# Peripherals.net
KiCad netlist of a schematic drawn in Altium Designer
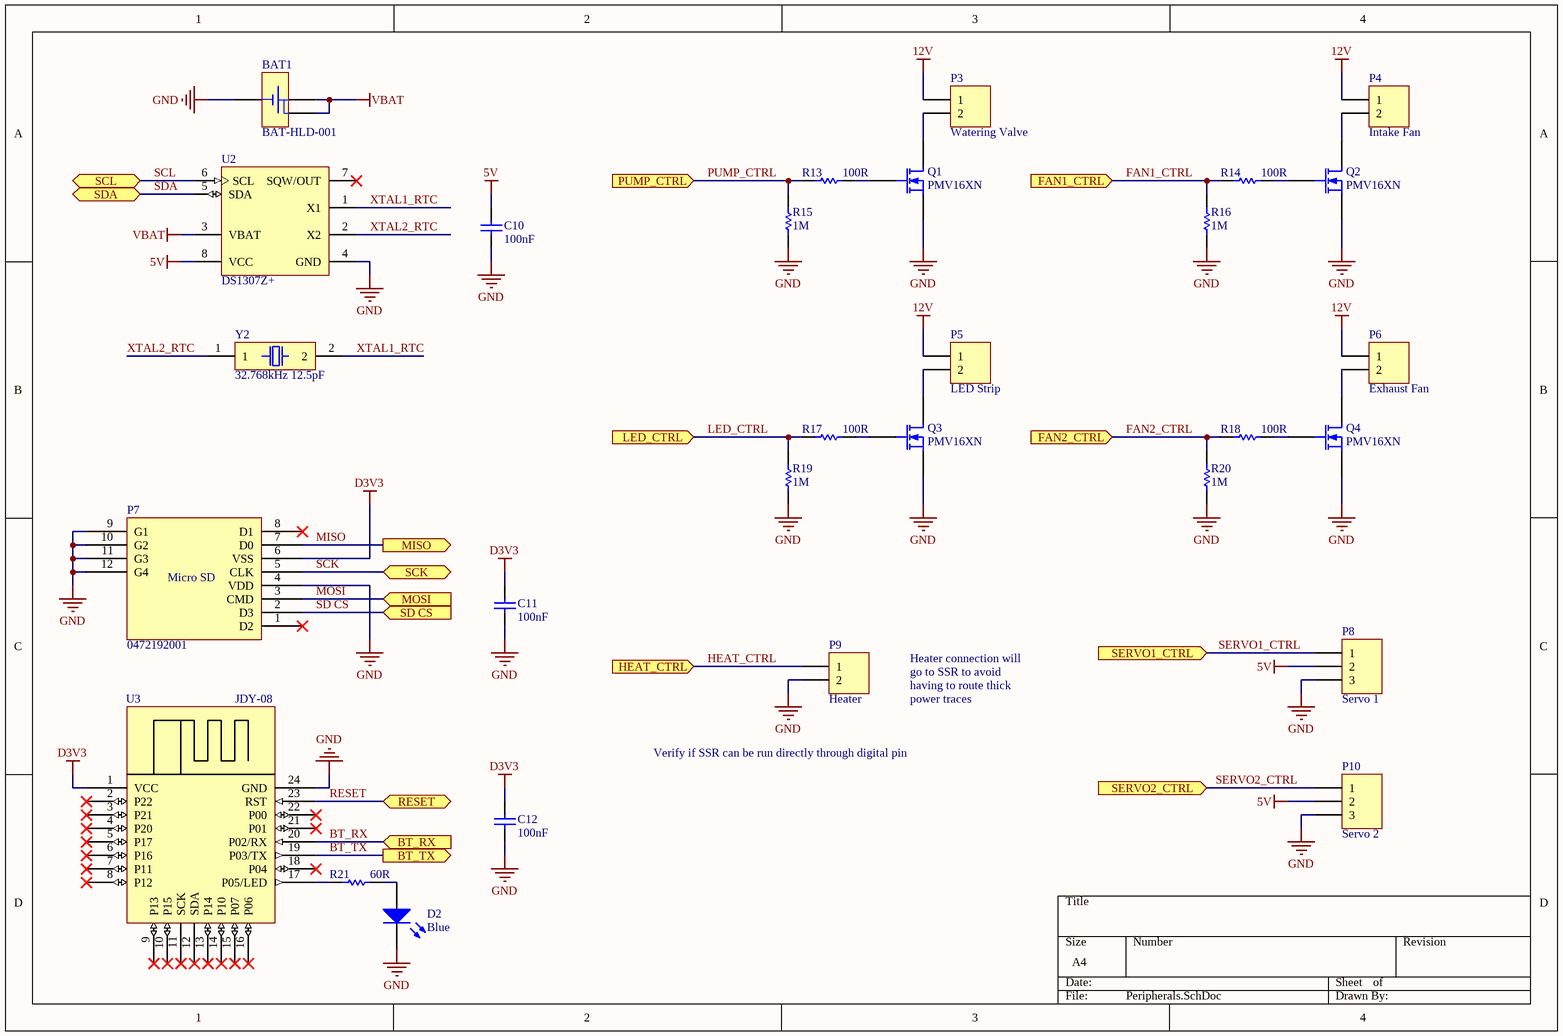
[diagram p0: Peripherals.SchDoc]

(export (version "E")
  (design (tool "Eeschema 10.0.6"))
  (components
    (comp (ref "BAT1")
      (value "BAT-HLD-001")
      (footprint "BATHLD-001")
      (description "20mm Coin Cell Battery Holder")
      (libsource (lib "Altium Content Vault") (part "BATHLD-001"))
    )
    (comp (ref "C10")
      (value "100nF")
      (footprint "CAP0603")
      (description "Capacitor")
      (fields (field (name "PUBLISHER") "Altium Limited"))
      (libsource (lib "Taiv") (part "Capacitor"))
    )
    (comp (ref "C11")
      (value "100nF")
      (footprint "CAP0603")
      (description "Capacitor")
      (fields (field (name "PUBLISHER") "Altium Limited"))
      (libsource (lib "Taiv") (part "Capacitor"))
    )
    (comp (ref "C12")
      (value "100nF")
      (footprint "CAP0603")
      (description "Capacitor")
      (fields (field (name "PUBLISHER") "Altium Limited"))
      (libsource (lib "Taiv") (part "Capacitor"))
    )
    (comp (ref "D2")
      (value "Blue")
      (footprint "DIODE0603")
      (description "Light Emitting Diode")
      (fields (field (name "PUBLISHER") "Altium Limited"))
      (libsource (lib "Taiv") (part "LED"))
    )
    (comp (ref "P3")
      (value "Watering Valve")
      (footprint "MOLEX MICROLATCH 2CT")
      (description "Header, 2-Pin")
      (fields (field (name "PUBLISHER") "Altium Limited"))
      (libsource (lib "Taiv") (part "2X1 2.54MM"))
    )
    (comp (ref "P4")
      (value "Intake Fan")
      (footprint "MOLEX MICROLATCH 2CT")
      (description "Header, 2-Pin")
      (fields (field (name "PUBLISHER") "Altium Limited"))
      (libsource (lib "Taiv") (part "2X1 2.54MM"))
    )
    (comp (ref "P5")
      (value "LED Strip")
      (footprint "MOLEX MICROLATCH 2CT")
      (description "Header, 2-Pin")
      (fields (field (name "PUBLISHER") "Altium Limited"))
      (libsource (lib "Taiv") (part "2X1 2.54MM"))
    )
    (comp (ref "P6")
      (value "Exhaust Fan")
      (footprint "MOLEX MICROLATCH 2CT")
      (description "Header, 2-Pin")
      (fields (field (name "PUBLISHER") "Altium Limited"))
      (libsource (lib "Taiv") (part "2X1 2.54MM"))
    )
    (comp (ref "P7")
      (value "0472192001")
      (footprint "MOLEX MICRO SD")
      (description "Micro SD Card")
      (libsource (lib "Taiv") (part "Micro SD Card"))
    )
    (comp (ref "P8")
      (value "Servo 1")
      (footprint "MOLEX MICROLATCH 3CT")
      (description "Header, 3-Pin")
      (fields (field (name "PUBLISHER") "Altium Limited"))
      (libsource (lib "Taiv") (part "3X1 2.54MM"))
    )
    (comp (ref "P9")
      (value "Heater")
      (footprint "MOLEX MICROLATCH 2CT")
      (description "Header, 2-Pin")
      (fields (field (name "PUBLISHER") "Altium Limited"))
      (libsource (lib "Taiv") (part "2X1 2.54MM"))
    )
    (comp (ref "P10")
      (value "Servo 2")
      (footprint "MOLEX MICROLATCH 3CT")
      (description "Header, 3-Pin")
      (fields (field (name "PUBLISHER") "Altium Limited"))
      (libsource (lib "Taiv") (part "3X1 2.54MM"))
    )
    (comp (ref "Q1")
      (value "PMV16XN")
      (footprint "SOT-23")
      (description "N-Channel MOSFET")
      (fields (field (name "PUBLISHER") "Altium Limited"))
      (libsource (lib "Taiv") (part "MOSFET-N"))
    )
    (comp (ref "Q2")
      (value "PMV16XN")
      (footprint "SOT-23")
      (description "N-Channel MOSFET")
      (fields (field (name "PUBLISHER") "Altium Limited"))
      (libsource (lib "Taiv") (part "MOSFET-N"))
    )
    (comp (ref "Q3")
      (value "PMV16XN")
      (footprint "SOT-23")
      (description "N-Channel MOSFET")
      (fields (field (name "PUBLISHER") "Altium Limited"))
      (libsource (lib "Taiv") (part "MOSFET-N"))
    )
    (comp (ref "Q4")
      (value "PMV16XN")
      (footprint "SOT-23")
      (description "N-Channel MOSFET")
      (fields (field (name "PUBLISHER") "Altium Limited"))
      (libsource (lib "Taiv") (part "MOSFET-N"))
    )
    (comp (ref "R13")
      (value "100R")
      (footprint "RES0603")
      (description "Resistor")
      (fields (field (name "PUBLISHER") "Altium Limited"))
      (libsource (lib "Taiv") (part "Resistor"))
    )
    (comp (ref "R14")
      (value "100R")
      (footprint "RES0603")
      (description "Resistor")
      (fields (field (name "PUBLISHER") "Altium Limited"))
      (libsource (lib "Taiv") (part "Resistor"))
    )
    (comp (ref "R15")
      (value "1M")
      (footprint "RES0603")
      (description "Resistor")
      (fields (field (name "PUBLISHER") "Altium Limited"))
      (libsource (lib "Taiv") (part "Resistor"))
    )
    (comp (ref "R16")
      (value "1M")
      (footprint "RES0603")
      (description "Resistor")
      (fields (field (name "PUBLISHER") "Altium Limited"))
      (libsource (lib "Taiv") (part "Resistor"))
    )
    (comp (ref "R17")
      (value "100R")
      (footprint "RES0603")
      (description "Resistor")
      (fields (field (name "PUBLISHER") "Altium Limited"))
      (libsource (lib "Taiv") (part "Resistor"))
    )
    (comp (ref "R18")
      (value "100R")
      (footprint "RES0603")
      (description "Resistor")
      (fields (field (name "PUBLISHER") "Altium Limited"))
      (libsource (lib "Taiv") (part "Resistor"))
    )
    (comp (ref "R19")
      (value "1M")
      (footprint "RES0603")
      (description "Resistor")
      (fields (field (name "PUBLISHER") "Altium Limited"))
      (libsource (lib "Taiv") (part "Resistor"))
    )
    (comp (ref "R20")
      (value "1M")
      (footprint "RES0603")
      (description "Resistor")
      (fields (field (name "PUBLISHER") "Altium Limited"))
      (libsource (lib "Taiv") (part "Resistor"))
    )
    (comp (ref "R21")
      (value "60R")
      (footprint "RES0603")
      (description "Resistor")
      (fields (field (name "PUBLISHER") "Altium Limited"))
      (libsource (lib "Taiv") (part "Resistor"))
    )
    (comp (ref "U2")
      (value "DS1307Z+")
      (footprint "SOIC8 150mil")
      (description "64 x 8, Serial, I2C Real-Time Clock, 5.0V, 8-Pin SO, 0 to 70 degC, Pb-Free")
      (libsource (lib "Taiv") (part "DS1307Z+"))
    )
    (comp (ref "U3")
      (value "JDY-08")
      (footprint "JDY-08")
      (description "HM-11 JDY-08 Bluetooth module")
      (libsource (lib "Taiv") (part "JDY-08"))
    )
    (comp (ref "Y2")
      (value "32.768kHz 12.5pF")
      (footprint "3210 XTAL")
      (description "XTAL 3210")
      (libsource (lib "Taiv") (part "XTAL 3210"))
    )
  )
  (nets
    (net (code "1") (name "/BT_RX") (class "Default")
      (node (ref "U3") (pin "20") (pinfunction "P02/RX_20") (pintype "input"))
    )
    (net (code "2") (name "/BT_TX") (class "Default")
      (node (ref "U3") (pin "19") (pinfunction "P03/TX_19") (pintype "output"))
    )
    (net (code "3") (name "/FAN1_CTRL") (class "Default")
      (node (ref "R14") (pin "2") (pinfunction "2_2") (pintype "passive"))
      (node (ref "R16") (pin "1") (pinfunction "1_1") (pintype "passive"))
    )
    (net (code "4") (name "/FAN2_CTRL") (class "Default")
      (node (ref "R18") (pin "2") (pinfunction "2_2") (pintype "passive"))
      (node (ref "R20") (pin "1") (pinfunction "1_1") (pintype "passive"))
    )
    (net (code "5") (name "/HEAT_CTRL") (class "Default")
      (node (ref "P9") (pin "1") (pinfunction "1_1") (pintype "passive"))
    )
    (net (code "6") (name "/LED_CTRL") (class "Default")
      (node (ref "R17") (pin "2") (pinfunction "2_2") (pintype "passive"))
      (node (ref "R19") (pin "1") (pinfunction "1_1") (pintype "passive"))
    )
    (net (code "7") (name "/MISO") (class "Default")
      (node (ref "P7") (pin "7") (pinfunction "D0_7") (pintype "passive"))
    )
    (net (code "8") (name "/MOSI") (class "Default")
      (node (ref "P7") (pin "3") (pinfunction "CMD_3") (pintype "passive"))
    )
    (net (code "9") (name "/PUMP_CTRL") (class "Default")
      (node (ref "R13") (pin "2") (pinfunction "2_2") (pintype "passive"))
      (node (ref "R15") (pin "1") (pinfunction "1_1") (pintype "passive"))
    )
    (net (code "10") (name "/RESET") (class "Default")
      (node (ref "U3") (pin "23") (pinfunction "RST_23") (pintype "input"))
    )
    (net (code "11") (name "/SCK") (class "Default")
      (node (ref "P7") (pin "5") (pinfunction "CLK_5") (pintype "passive"))
    )
    (net (code "12") (name "/SCL") (class "Default")
      (node (ref "U2") (pin "6") (pinfunction "SCL_6") (pintype "input"))
    )
    (net (code "13") (name "/SD CS") (class "Default")
      (node (ref "P7") (pin "2") (pinfunction "D3_2") (pintype "passive"))
    )
    (net (code "14") (name "/SDA") (class "Default")
      (node (ref "U2") (pin "5") (pinfunction "SDA_5") (pintype "bidirectional"))
    )
    (net (code "15") (name "/SERVO1_CTRL") (class "Default")
      (node (ref "P8") (pin "1") (pinfunction "1_1") (pintype "passive"))
    )
    (net (code "16") (name "/SERVO2_CTRL") (class "Default")
      (node (ref "P10") (pin "1") (pinfunction "1_1") (pintype "passive"))
    )
    (net (code "17") (name "/XTAL1_RTC") (class "Default")
      (node (ref "U2") (pin "1") (pinfunction "X1_1") (pintype "passive"))
      (node (ref "Y2") (pin "2") (pinfunction "2_2") (pintype "passive"))
    )
    (net (code "18") (name "/XTAL2_RTC") (class "Default")
      (node (ref "U2") (pin "2") (pinfunction "X2_2") (pintype "passive"))
      (node (ref "Y2") (pin "1") (pinfunction "1_1") (pintype "passive"))
    )
    (net (code "19") (name "5V") (class "Default")
      (node (ref "C10") (pin "2") (pinfunction "2_2") (pintype "passive"))
      (node (ref "P10") (pin "2") (pinfunction "2_2") (pintype "passive"))
      (node (ref "P8") (pin "2") (pinfunction "2_2") (pintype "passive"))
      (node (ref "U2") (pin "8") (pinfunction "VCC_8") (pintype "power_in"))
    )
    (net (code "20") (name "12V") (class "Default")
      (node (ref "P3") (pin "1") (pinfunction "1_1") (pintype "passive"))
      (node (ref "P4") (pin "1") (pinfunction "1_1") (pintype "passive"))
      (node (ref "P5") (pin "1") (pinfunction "1_1") (pintype "passive"))
      (node (ref "P6") (pin "1") (pinfunction "1_1") (pintype "passive"))
    )
    (net (code "21") (name "D3V3") (class "Default")
      (node (ref "C11") (pin "2") (pinfunction "2_2") (pintype "passive"))
      (node (ref "C12") (pin "2") (pinfunction "2_2") (pintype "passive"))
      (node (ref "P7") (pin "6") (pinfunction "VSS_6") (pintype "passive"))
      (node (ref "U3") (pin "1") (pinfunction "VCC_1") (pintype "power_in"))
    )
    (net (code "22") (name "GND") (class "Default")
      (node (ref "BAT1") (pin "1") (pinfunction "-_1") (pintype "passive"))
      (node (ref "C10") (pin "1") (pinfunction "1_1") (pintype "passive"))
      (node (ref "C11") (pin "1") (pinfunction "1_1") (pintype "passive"))
      (node (ref "C12") (pin "1") (pinfunction "1_1") (pintype "passive"))
      (node (ref "D2") (pin "2") (pinfunction "K_2") (pintype "passive"))
      (node (ref "P10") (pin "3") (pinfunction "3_3") (pintype "passive"))
      (node (ref "P7") (pin "10") (pinfunction "G2_10") (pintype "passive"))
      (node (ref "P7") (pin "11") (pinfunction "G3_11") (pintype "passive"))
      (node (ref "P7") (pin "12") (pinfunction "G4_12") (pintype "passive"))
      (node (ref "P7") (pin "4") (pinfunction "VDD_4") (pintype "passive"))
      (node (ref "P7") (pin "9") (pinfunction "G1_9") (pintype "passive"))
      (node (ref "P8") (pin "3") (pinfunction "3_3") (pintype "passive"))
      (node (ref "P9") (pin "2") (pinfunction "2_2") (pintype "passive"))
      (node (ref "Q1") (pin "2") (pinfunction "S_2") (pintype "passive"))
      (node (ref "Q2") (pin "2") (pinfunction "S_2") (pintype "passive"))
      (node (ref "Q3") (pin "2") (pinfunction "S_2") (pintype "passive"))
      (node (ref "Q4") (pin "2") (pinfunction "S_2") (pintype "passive"))
      (node (ref "R15") (pin "2") (pinfunction "2_2") (pintype "passive"))
      (node (ref "R16") (pin "2") (pinfunction "2_2") (pintype "passive"))
      (node (ref "R19") (pin "2") (pinfunction "2_2") (pintype "passive"))
      (node (ref "R20") (pin "2") (pinfunction "2_2") (pintype "passive"))
      (node (ref "U2") (pin "4") (pinfunction "GND_4") (pintype "power_in"))
      (node (ref "U3") (pin "24") (pinfunction "GND_24") (pintype "power_in"))
    )
    (net (code "23") (name "Net-(D2-A)") (class "Default")
      (node (ref "D2") (pin "1") (pinfunction "A_1") (pintype "passive"))
      (node (ref "R21") (pin "1") (pinfunction "1_1") (pintype "passive"))
    )
    (net (code "24") (name "Net-(Q1-D)") (class "Default")
      (node (ref "P3") (pin "2") (pinfunction "2_2") (pintype "passive"))
      (node (ref "Q1") (pin "3") (pinfunction "D_3") (pintype "passive"))
    )
    (net (code "25") (name "Net-(Q1-G)") (class "Default")
      (node (ref "Q1") (pin "1") (pinfunction "G_1") (pintype "passive"))
      (node (ref "R13") (pin "1") (pinfunction "1_1") (pintype "passive"))
    )
    (net (code "26") (name "Net-(Q2-D)") (class "Default")
      (node (ref "P4") (pin "2") (pinfunction "2_2") (pintype "passive"))
      (node (ref "Q2") (pin "3") (pinfunction "D_3") (pintype "passive"))
    )
    (net (code "27") (name "Net-(Q2-G)") (class "Default")
      (node (ref "Q2") (pin "1") (pinfunction "G_1") (pintype "passive"))
      (node (ref "R14") (pin "1") (pinfunction "1_1") (pintype "passive"))
    )
    (net (code "28") (name "Net-(Q3-D)") (class "Default")
      (node (ref "P5") (pin "2") (pinfunction "2_2") (pintype "passive"))
      (node (ref "Q3") (pin "3") (pinfunction "D_3") (pintype "passive"))
    )
    (net (code "29") (name "Net-(Q3-G)") (class "Default")
      (node (ref "Q3") (pin "1") (pinfunction "G_1") (pintype "passive"))
      (node (ref "R17") (pin "1") (pinfunction "1_1") (pintype "passive"))
    )
    (net (code "30") (name "Net-(Q4-D)") (class "Default")
      (node (ref "P6") (pin "2") (pinfunction "2_2") (pintype "passive"))
      (node (ref "Q4") (pin "3") (pinfunction "D_3") (pintype "passive"))
    )
    (net (code "31") (name "Net-(Q4-G)") (class "Default")
      (node (ref "Q4") (pin "1") (pinfunction "G_1") (pintype "passive"))
      (node (ref "R18") (pin "1") (pinfunction "1_1") (pintype "passive"))
    )
    (net (code "32") (name "Net-(U3-P05{slash}LED)") (class "Default")
      (node (ref "R21") (pin "2") (pinfunction "2_2") (pintype "passive"))
      (node (ref "U3") (pin "17") (pinfunction "P05/LED_17") (pintype "output"))
    )
    (net (code "33") (name "VBAT") (class "Default")
      (node (ref "BAT1") (pin "2") (pinfunction "+_2") (pintype "passive"))
      (node (ref "BAT1") (pin "3") (pinfunction "+_3") (pintype "passive"))
      (node (ref "U2") (pin "3") (pinfunction "VBAT_3") (pintype "power_in"))
    )
    (net (code "34") (name "unconnected-(P7-D1-Pad8)") (class "Default")
      (node (ref "P7") (pin "8") (pinfunction "D1_8") (pintype "passive+no_connect"))
    )
    (net (code "35") (name "unconnected-(P7-D2-Pad1)") (class "Default")
      (node (ref "P7") (pin "1") (pinfunction "D2_1") (pintype "passive+no_connect"))
    )
    (net (code "36") (name "unconnected-(U2-SQW{slash}OUT-Pad7)") (class "Default")
      (node (ref "U2") (pin "7") (pinfunction "SQW/OUT_7") (pintype "open_collector+no_connect"))
    )
    (net (code "37") (name "unconnected-(U3-P00-Pad22)") (class "Default")
      (node (ref "U3") (pin "22") (pinfunction "P00_22") (pintype "bidirectional+no_connect"))
    )
    (net (code "38") (name "unconnected-(U3-P01-Pad21)") (class "Default")
      (node (ref "U3") (pin "21") (pinfunction "P01_21") (pintype "bidirectional+no_connect"))
    )
    (net (code "39") (name "unconnected-(U3-P04-Pad18)") (class "Default")
      (node (ref "U3") (pin "18") (pinfunction "P04_18") (pintype "bidirectional+no_connect"))
    )
    (net (code "40") (name "unconnected-(U3-P06-Pad16)") (class "Default")
      (node (ref "U3") (pin "16") (pinfunction "P06_16") (pintype "bidirectional+no_connect"))
    )
    (net (code "41") (name "unconnected-(U3-P07-Pad15)") (class "Default")
      (node (ref "U3") (pin "15") (pinfunction "P07_15") (pintype "bidirectional+no_connect"))
    )
    (net (code "42") (name "unconnected-(U3-P10-Pad14)") (class "Default")
      (node (ref "U3") (pin "14") (pinfunction "P10_14") (pintype "bidirectional+no_connect"))
    )
    (net (code "43") (name "unconnected-(U3-P11-Pad7)") (class "Default")
      (node (ref "U3") (pin "7") (pinfunction "P11_7") (pintype "bidirectional+no_connect"))
    )
    (net (code "44") (name "unconnected-(U3-P12-Pad8)") (class "Default")
      (node (ref "U3") (pin "8") (pinfunction "P12_8") (pintype "bidirectional+no_connect"))
    )
    (net (code "45") (name "unconnected-(U3-P13-Pad9)") (class "Default")
      (node (ref "U3") (pin "9") (pinfunction "P13_9") (pintype "bidirectional+no_connect"))
    )
    (net (code "46") (name "unconnected-(U3-P14-Pad13)") (class "Default")
      (node (ref "U3") (pin "13") (pinfunction "P14_13") (pintype "bidirectional+no_connect"))
    )
    (net (code "47") (name "unconnected-(U3-P15-Pad10)") (class "Default")
      (node (ref "U3") (pin "10") (pinfunction "P15_10") (pintype "bidirectional+no_connect"))
    )
    (net (code "48") (name "unconnected-(U3-P16-Pad6)") (class "Default")
      (node (ref "U3") (pin "6") (pinfunction "P16_6") (pintype "bidirectional+no_connect"))
    )
    (net (code "49") (name "unconnected-(U3-P17-Pad5)") (class "Default")
      (node (ref "U3") (pin "5") (pinfunction "P17_5") (pintype "bidirectional+no_connect"))
    )
    (net (code "50") (name "unconnected-(U3-P20-Pad4)") (class "Default")
      (node (ref "U3") (pin "4") (pinfunction "P20_4") (pintype "bidirectional+no_connect"))
    )
    (net (code "51") (name "unconnected-(U3-P21-Pad3)") (class "Default")
      (node (ref "U3") (pin "3") (pinfunction "P21_3") (pintype "bidirectional+no_connect"))
    )
    (net (code "52") (name "unconnected-(U3-P22-Pad2)") (class "Default")
      (node (ref "U3") (pin "2") (pinfunction "P22_2") (pintype "bidirectional+no_connect"))
    )
    (net (code "53") (name "unconnected-(U3-SCK-Pad11)") (class "Default")
      (node (ref "U3") (pin "11") (pinfunction "SCK_11") (pintype "passive+no_connect"))
    )
    (net (code "54") (name "unconnected-(U3-SDA-Pad12)") (class "Default")
      (node (ref "U3") (pin "12") (pinfunction "SDA_12") (pintype "passive+no_connect"))
    )
  )
)
